# sa_psu.net
KiCad netlist of a schematic drawn in EAGLE
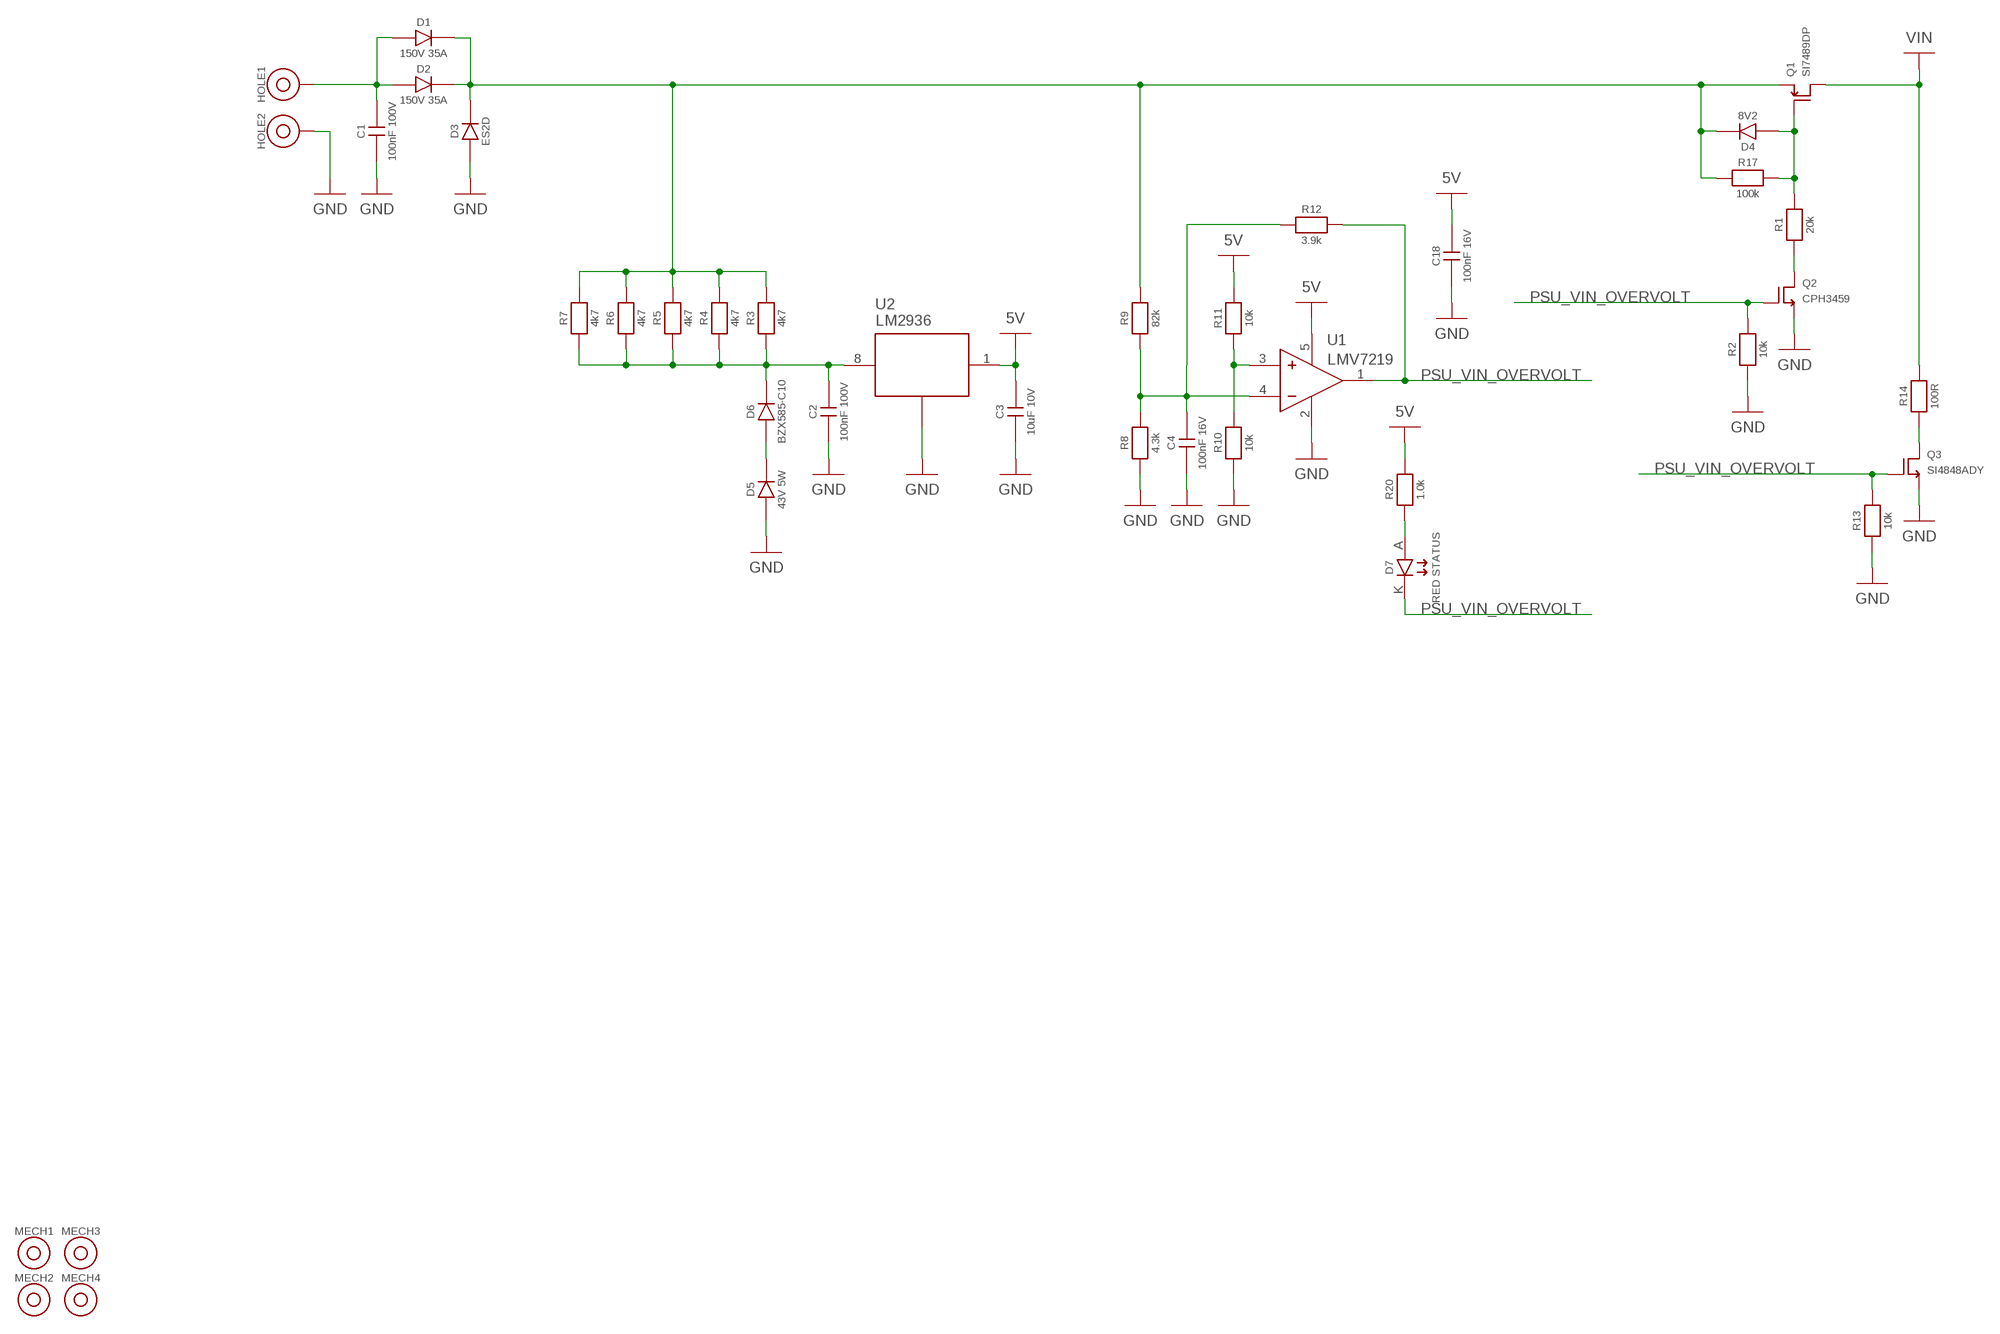
[diagram p0: schematic, sheet 1, part 1 of 2]
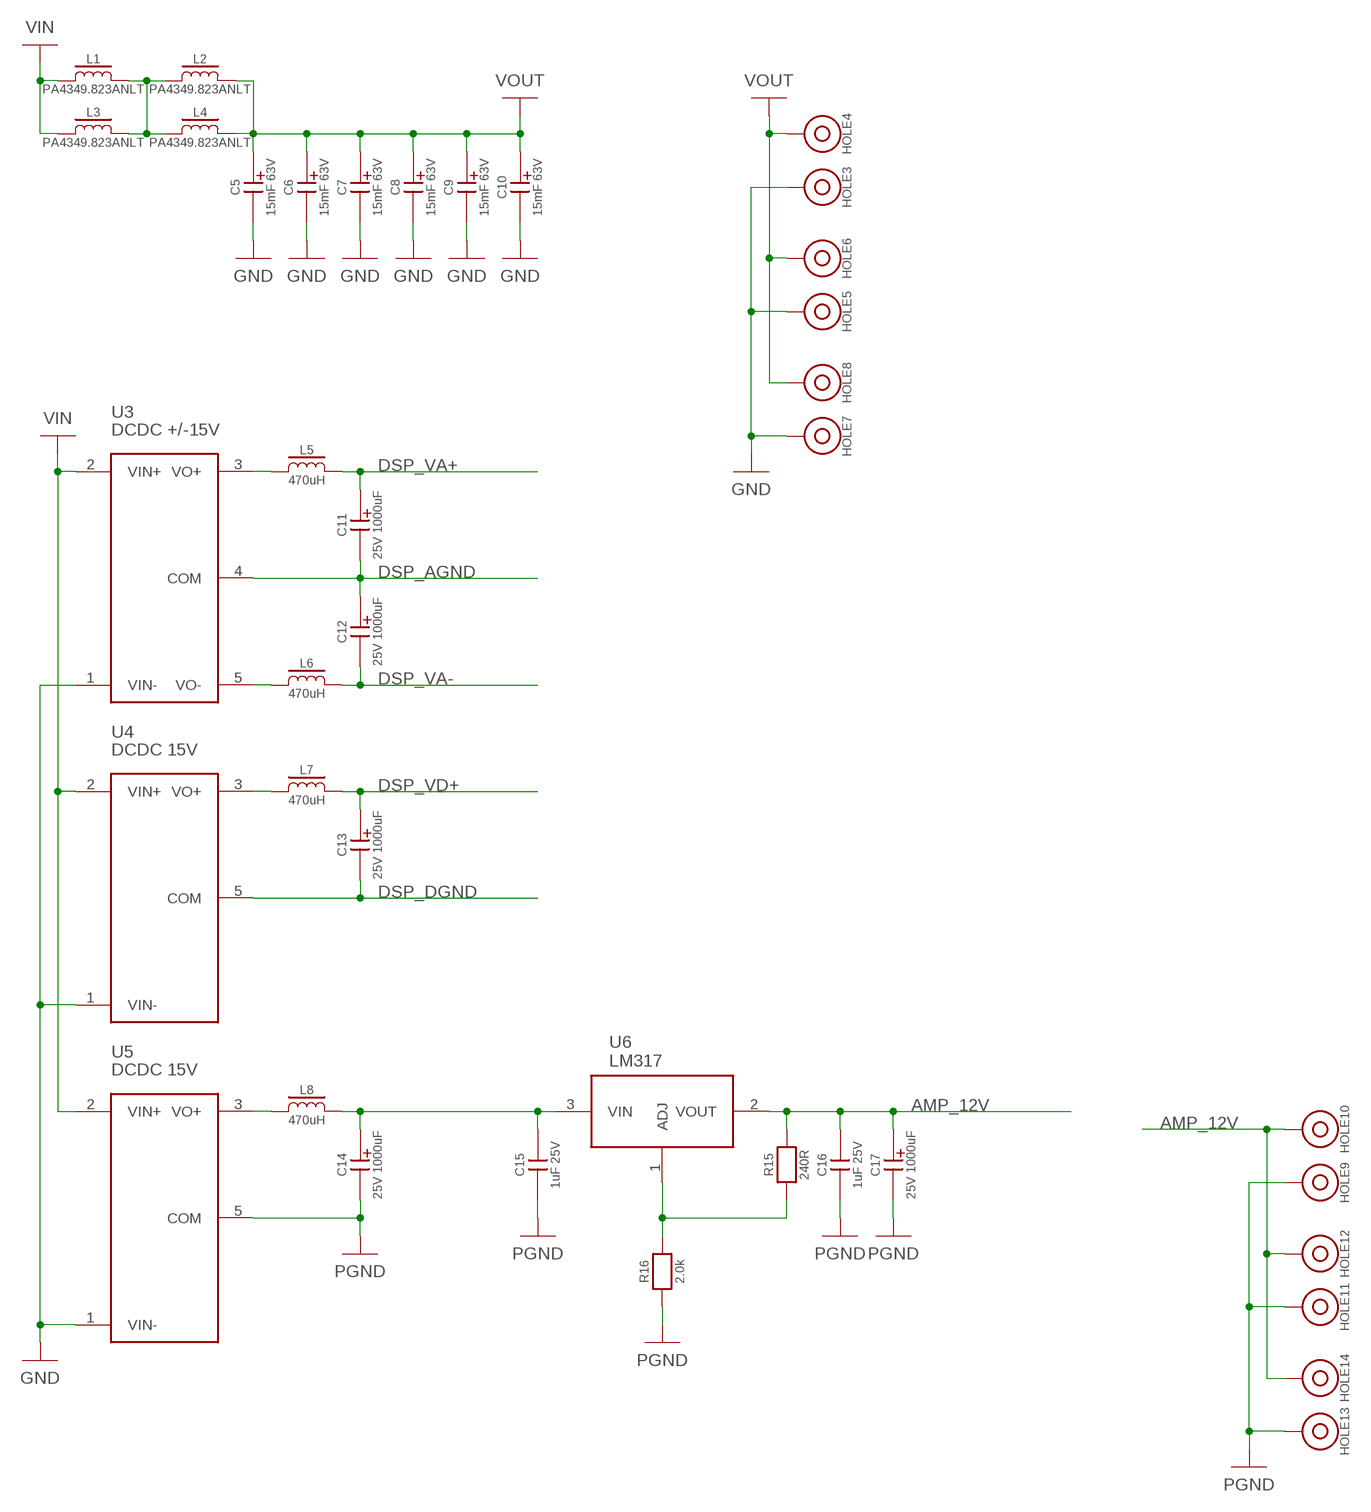
[diagram p1: schematic, sheet 1, part 2 of 2]

(export (version "E")
  (design (tool "Eeschema 10.0.6"))
  (components
    (comp (ref "C1")
      (value "100nF 100V")
      (footprint "eagle-import:0603")
      (libsource (lib "eagle-import") (part "06031C104KAT2A"))
    )
    (comp (ref "C2")
      (value "100nF 100V")
      (footprint "eagle-import:0603")
      (libsource (lib "eagle-import") (part "06031C104KAT2A"))
    )
    (comp (ref "C3")
      (value "10uF 10V")
      (footprint "eagle-import:0603")
      (libsource (lib "eagle-import") (part "GRM188R61A106KE69D"))
    )
    (comp (ref "C4")
      (value "100nF 16V")
      (footprint "eagle-import:0603")
      (libsource (lib "eagle-import") (part "CL10B104KO8WPNC"))
    )
    (comp (ref "C5")
      (value "15mF 63V")
      (footprint "eagle-import:35MM_10MMCAP")
      (libsource (lib "eagle-import") (part "C_ELEC35MM"))
    )
    (comp (ref "C6")
      (value "15mF 63V")
      (footprint "eagle-import:35MM_10MMCAP")
      (libsource (lib "eagle-import") (part "C_ELEC35MM"))
    )
    (comp (ref "C7")
      (value "15mF 63V")
      (footprint "eagle-import:35MM_10MMCAP")
      (libsource (lib "eagle-import") (part "C_ELEC35MM"))
    )
    (comp (ref "C8")
      (value "15mF 63V")
      (footprint "eagle-import:35MM_10MMCAP")
      (libsource (lib "eagle-import") (part "C_ELEC35MM"))
    )
    (comp (ref "C9")
      (value "15mF 63V")
      (footprint "eagle-import:35MM_10MMCAP")
      (libsource (lib "eagle-import") (part "C_ELEC35MM"))
    )
    (comp (ref "C10")
      (value "15mF 63V")
      (footprint "eagle-import:35MM_10MMCAP")
      (libsource (lib "eagle-import") (part "C_ELEC35MM"))
    )
    (comp (ref "C11")
      (value "25V 1000uF")
      (footprint "eagle-import:10MM_RADIAL_5MM_PITCH")
      (libsource (lib "eagle-import") (part "25ZLJ1000M10X20"))
    )
    (comp (ref "C12")
      (value "25V 1000uF")
      (footprint "eagle-import:10MM_RADIAL_5MM_PITCH")
      (libsource (lib "eagle-import") (part "25ZLJ1000M10X20"))
    )
    (comp (ref "C13")
      (value "25V 1000uF")
      (footprint "eagle-import:10MM_RADIAL_5MM_PITCH")
      (libsource (lib "eagle-import") (part "25ZLJ1000M10X20"))
    )
    (comp (ref "C14")
      (value "25V 1000uF")
      (footprint "eagle-import:10MM_RADIAL_5MM_PITCH")
      (libsource (lib "eagle-import") (part "25ZLJ1000M10X20"))
    )
    (comp (ref "C15")
      (value "1uF 25V")
      (footprint "eagle-import:0603")
      (libsource (lib "eagle-import") (part "CL10A105KA8NNNC"))
    )
    (comp (ref "C16")
      (value "1uF 25V")
      (footprint "eagle-import:0603")
      (libsource (lib "eagle-import") (part "CL10A105KA8NNNC"))
    )
    (comp (ref "C17")
      (value "25V 1000uF")
      (footprint "eagle-import:10MM_RADIAL_5MM_PITCH")
      (libsource (lib "eagle-import") (part "25ZLJ1000M10X20"))
    )
    (comp (ref "C18")
      (value "100nF 16V")
      (footprint "eagle-import:0603")
      (libsource (lib "eagle-import") (part "CL10B104KO8WPNC"))
    )
    (comp (ref "D1")
      (value "150V 35A")
      (footprint "eagle-import:TO252")
      (libsource (lib "eagle-import") (part "V35PW15-M3/I"))
    )
    (comp (ref "D2")
      (value "150V 35A")
      (footprint "eagle-import:TO252")
      (libsource (lib "eagle-import") (part "V35PW15-M3/I"))
    )
    (comp (ref "D3")
      (value "ES2D")
      (footprint "eagle-import:DO214AA")
      (libsource (lib "eagle-import") (part "ES2D"))
    )
    (comp (ref "D4")
      (value "8V2")
      (footprint "eagle-import:SOD80")
      (libsource (lib "eagle-import") (part "BZT55C8V2"))
    )
    (comp (ref "D5")
      (value "43V 5W")
      (footprint "eagle-import:017AA-01")
      (libsource (lib "eagle-import") (part "1N5367BG"))
    )
    (comp (ref "D6")
      (value "BZX585-C10")
      (footprint "eagle-import:SOD_523")
      (libsource (lib "eagle-import") (part "BZX585-C10"))
    )
    (comp (ref "D7")
      (value "RED STATUS")
      (footprint "eagle-import:VLMT3100")
      (libsource (lib "eagle-import") (part "VLMT3100-GS08"))
    )
    (comp (ref "HOLE1")
      (value "4mm ID")
      (footprint "eagle-import:MOUNTHOLE_8X4")
      (libsource (lib "eagle-import") (part "MOUNTHOLE_METAL"))
    )
    (comp (ref "HOLE2")
      (value "4mm ID")
      (footprint "eagle-import:MOUNTHOLE_8X4")
      (libsource (lib "eagle-import") (part "MOUNTHOLE_METAL"))
    )
    (comp (ref "HOLE3")
      (value "4mm ID")
      (footprint "eagle-import:MOUNTHOLE_8X4")
      (libsource (lib "eagle-import") (part "MOUNTHOLE_METAL"))
    )
    (comp (ref "HOLE4")
      (value "4mm ID")
      (footprint "eagle-import:MOUNTHOLE_8X4")
      (libsource (lib "eagle-import") (part "MOUNTHOLE_METAL"))
    )
    (comp (ref "HOLE5")
      (value "4mm ID")
      (footprint "eagle-import:MOUNTHOLE_8X4")
      (libsource (lib "eagle-import") (part "MOUNTHOLE_METAL"))
    )
    (comp (ref "HOLE6")
      (value "4mm ID")
      (footprint "eagle-import:MOUNTHOLE_8X4")
      (libsource (lib "eagle-import") (part "MOUNTHOLE_METAL"))
    )
    (comp (ref "HOLE7")
      (value "4mm ID")
      (footprint "eagle-import:MOUNTHOLE_8X4")
      (libsource (lib "eagle-import") (part "MOUNTHOLE_METAL"))
    )
    (comp (ref "HOLE8")
      (value "4mm ID")
      (footprint "eagle-import:MOUNTHOLE_8X4")
      (libsource (lib "eagle-import") (part "MOUNTHOLE_METAL"))
    )
    (comp (ref "HOLE9")
      (value "MOUNTHOLE_METAL4X2")
      (footprint "eagle-import:4X2")
      (libsource (lib "eagle-import") (part "MOUNTHOLE_METAL4X2"))
    )
    (comp (ref "HOLE10")
      (value "MOUNTHOLE_METAL4X2")
      (footprint "eagle-import:4X2")
      (libsource (lib "eagle-import") (part "MOUNTHOLE_METAL4X2"))
    )
    (comp (ref "HOLE11")
      (value "MOUNTHOLE_METAL4X2")
      (footprint "eagle-import:4X2")
      (libsource (lib "eagle-import") (part "MOUNTHOLE_METAL4X2"))
    )
    (comp (ref "HOLE12")
      (value "MOUNTHOLE_METAL4X2")
      (footprint "eagle-import:4X2")
      (libsource (lib "eagle-import") (part "MOUNTHOLE_METAL4X2"))
    )
    (comp (ref "HOLE13")
      (value "MOUNTHOLE_METAL4X2")
      (footprint "eagle-import:4X2")
      (libsource (lib "eagle-import") (part "MOUNTHOLE_METAL4X2"))
    )
    (comp (ref "HOLE14")
      (value "MOUNTHOLE_METAL4X2")
      (footprint "eagle-import:4X2")
      (libsource (lib "eagle-import") (part "MOUNTHOLE_METAL4X2"))
    )
    (comp (ref "L1")
      (value "PA4349.823ANLT")
      (footprint "eagle-import:PA4349.ZZZANLT")
      (libsource (lib "eagle-import") (part "PA4349.823ANLT"))
    )
    (comp (ref "L2")
      (value "PA4349.823ANLT")
      (footprint "eagle-import:PA4349.ZZZANLT")
      (libsource (lib "eagle-import") (part "PA4349.823ANLT"))
    )
    (comp (ref "L3")
      (value "PA4349.823ANLT")
      (footprint "eagle-import:PA4349.ZZZANLT")
      (libsource (lib "eagle-import") (part "PA4349.823ANLT"))
    )
    (comp (ref "L4")
      (value "PA4349.823ANLT")
      (footprint "eagle-import:PA4349.ZZZANLT")
      (libsource (lib "eagle-import") (part "PA4349.823ANLT"))
    )
    (comp (ref "L5")
      (value "470uH")
      (footprint "eagle-import:SRN1060")
      (libsource (lib "eagle-import") (part "SRN1060-471M"))
    )
    (comp (ref "L6")
      (value "470uH")
      (footprint "eagle-import:SRN1060")
      (libsource (lib "eagle-import") (part "SRN1060-471M"))
    )
    (comp (ref "L7")
      (value "470uH")
      (footprint "eagle-import:SRN1060")
      (libsource (lib "eagle-import") (part "SRN1060-471M"))
    )
    (comp (ref "L8")
      (value "470uH")
      (footprint "eagle-import:SRN1060")
      (libsource (lib "eagle-import") (part "SRN1060-471M"))
    )
    (comp (ref "MECH1")
      (value "6mm x 3mm")
      (footprint "eagle-import:MOUNTHOLE_6X3")
      (libsource (lib "eagle-import") (part "MOUNTHOLE"))
    )
    (comp (ref "MECH2")
      (value "6mm x 3mm")
      (footprint "eagle-import:MOUNTHOLE_6X3")
      (libsource (lib "eagle-import") (part "MOUNTHOLE"))
    )
    (comp (ref "MECH3")
      (value "6mm x 3mm")
      (footprint "eagle-import:MOUNTHOLE_6X3")
      (libsource (lib "eagle-import") (part "MOUNTHOLE"))
    )
    (comp (ref "MECH4")
      (value "6mm x 3mm")
      (footprint "eagle-import:MOUNTHOLE_6X3")
      (libsource (lib "eagle-import") (part "MOUNTHOLE"))
    )
    (comp (ref "Q1")
      (value "SI7489DP")
      (footprint "eagle-import:SO8_POWERPAK")
      (libsource (lib "eagle-import") (part "SI7489DP-T1-E3"))
    )
    (comp (ref "Q2")
      (value "CPH3459")
      (footprint "eagle-import:SOT23-3")
      (libsource (lib "eagle-import") (part "CPH3459-TL-W"))
    )
    (comp (ref "Q3")
      (value "SI4848ADY")
      (footprint "eagle-import:SO8")
      (libsource (lib "eagle-import") (part "SI4848ADY-T1-GE3"))
    )
    (comp (ref "R1")
      (value "20k")
      (footprint "eagle-import:0603")
      (libsource (lib "eagle-import") (part "ERJ3EKF2002V"))
    )
    (comp (ref "R2")
      (value "10k")
      (footprint "eagle-import:0603")
      (libsource (lib "eagle-import") (part "ERJ3EKF1002V"))
    )
    (comp (ref "R3")
      (value "4k7")
      (footprint "eagle-import:1206")
      (libsource (lib "eagle-import") (part "CRCW12064K70FKEAHP"))
    )
    (comp (ref "R4")
      (value "4k7")
      (footprint "eagle-import:1206")
      (libsource (lib "eagle-import") (part "CRCW12064K70FKEAHP"))
    )
    (comp (ref "R5")
      (value "4k7")
      (footprint "eagle-import:1206")
      (libsource (lib "eagle-import") (part "CRCW12064K70FKEAHP"))
    )
    (comp (ref "R6")
      (value "4k7")
      (footprint "eagle-import:1206")
      (libsource (lib "eagle-import") (part "CRCW12064K70FKEAHP"))
    )
    (comp (ref "R7")
      (value "4k7")
      (footprint "eagle-import:1206")
      (libsource (lib "eagle-import") (part "CRCW12064K70FKEAHP"))
    )
    (comp (ref "R8")
      (value "4.3k")
      (footprint "eagle-import:0603")
      (libsource (lib "eagle-import") (part "ERJ3EKF4301V"))
    )
    (comp (ref "R9")
      (value "82k")
      (footprint "eagle-import:0603")
      (libsource (lib "eagle-import") (part "ERJ3EKF8202V"))
    )
    (comp (ref "R10")
      (value "10k")
      (footprint "eagle-import:0603")
      (libsource (lib "eagle-import") (part "ERJ3EKF1002V"))
    )
    (comp (ref "R11")
      (value "10k")
      (footprint "eagle-import:0603")
      (libsource (lib "eagle-import") (part "ERJ3EKF1002V"))
    )
    (comp (ref "R12")
      (value "3.9k")
      (footprint "eagle-import:0603")
      (libsource (lib "eagle-import") (part "ERJ3EKF3901V"))
    )
    (comp (ref "R13")
      (value "10k")
      (footprint "eagle-import:0603")
      (libsource (lib "eagle-import") (part "ERJ3EKF1002V"))
    )
    (comp (ref "R14")
      (value "100R")
      (footprint "eagle-import:15MM_TH")
      (libsource (lib "eagle-import") (part "ERG-3SJ101V"))
    )
    (comp (ref "R15")
      (value "240R")
      (footprint "eagle-import:0603")
      (libsource (lib "eagle-import") (part "ERJ3EKF2400V"))
    )
    (comp (ref "R16")
      (value "2.0k")
      (footprint "eagle-import:0603")
      (libsource (lib "eagle-import") (part "ERJ3EKF2001V"))
    )
    (comp (ref "R17")
      (value "100k")
      (footprint "eagle-import:0603")
      (libsource (lib "eagle-import") (part "ERJ3EKF1003V"))
    )
    (comp (ref "R20")
      (value "1.0k")
      (footprint "eagle-import:0603")
      (libsource (lib "eagle-import") (part "ERJ3EKF1001V"))
    )
    (comp (ref "U1")
      (value "LMV7219")
      (footprint "eagle-import:SOT23-5")
      (libsource (lib "eagle-import") (part "LMV7219M5/NOPB"))
    )
    (comp (ref "U2")
      (value "LM2936")
      (footprint "eagle-import:SO8")
      (libsource (lib "eagle-import") (part "LM2936HVMAX"))
    )
    (comp (ref "U3")
      (value "DCDC +/-15V")
      (footprint "eagle-import:PDQE10")
      (libsource (lib "eagle-import") (part "PDQE10-Q48-D15-D"))
    )
    (comp (ref "U4")
      (value "DCDC 15V")
      (footprint "eagle-import:PDQE10")
      (libsource (lib "eagle-import") (part "PDQE10-Q48-S15"))
    )
    (comp (ref "U5")
      (value "DCDC 15V")
      (footprint "eagle-import:PDQE10")
      (libsource (lib "eagle-import") (part "PDQE10-Q48-S15"))
    )
    (comp (ref "U6")
      (value "LM317")
      (footprint "eagle-import:TO220")
      (libsource (lib "eagle-import") (part "LM317T"))
    )
  )
  (nets
    (net (code "1") (name "/AMP_12V") (class "Default")
      (node (ref "C16") (pin "2") (pinfunction "2_2") (pintype "bidirectional"))
      (node (ref "C17") (pin "2") (pinfunction "A_2") (pintype "bidirectional"))
      (node (ref "HOLE10") (pin "1") (pinfunction "1_1") (pintype "bidirectional"))
      (node (ref "HOLE12") (pin "1") (pinfunction "1_1") (pintype "bidirectional"))
      (node (ref "HOLE14") (pin "1") (pinfunction "1_1") (pintype "bidirectional"))
      (node (ref "R15") (pin "2") (pinfunction "2_2") (pintype "bidirectional"))
      (node (ref "U6") (pin "2") (pinfunction "VOUT_2") (pintype "bidirectional"))
    )
    (net (code "2") (name "/DSP_AGND") (class "Default")
      (node (ref "C11") (pin "1") (pinfunction "K_1") (pintype "bidirectional"))
      (node (ref "C12") (pin "2") (pinfunction "A_2") (pintype "bidirectional"))
      (node (ref "U3") (pin "4") (pinfunction "COM_4") (pintype "bidirectional"))
    )
    (net (code "3") (name "/DSP_DGND") (class "Default")
      (node (ref "C13") (pin "1") (pinfunction "K_1") (pintype "bidirectional"))
      (node (ref "U4") (pin "5") (pinfunction "COM_5") (pintype "bidirectional"))
    )
    (net (code "4") (name "/DSP_VA+") (class "Default")
      (node (ref "C11") (pin "2") (pinfunction "A_2") (pintype "bidirectional"))
      (node (ref "L5") (pin "2") (pinfunction "2_2") (pintype "bidirectional"))
    )
    (net (code "5") (name "/DSP_VA-") (class "Default")
      (node (ref "C12") (pin "1") (pinfunction "K_1") (pintype "bidirectional"))
      (node (ref "L6") (pin "2") (pinfunction "2_2") (pintype "bidirectional"))
    )
    (net (code "6") (name "/DSP_VD+") (class "Default")
      (node (ref "C13") (pin "2") (pinfunction "A_2") (pintype "bidirectional"))
      (node (ref "L7") (pin "2") (pinfunction "2_2") (pintype "bidirectional"))
    )
    (net (code "7") (name "/PSU_VIN_OVERVOLT") (class "Default")
      (node (ref "D7") (pin "K") (pinfunction "K_K") (pintype "bidirectional"))
      (node (ref "Q2") (pin "1") (pinfunction "G_1") (pintype "bidirectional"))
      (node (ref "Q3") (pin "4") (pinfunction "G_4") (pintype "bidirectional"))
      (node (ref "R12") (pin "2") (pinfunction "2_2") (pintype "bidirectional"))
      (node (ref "R13") (pin "2") (pinfunction "2_2") (pintype "bidirectional"))
      (node (ref "R2") (pin "2") (pinfunction "2_2") (pintype "bidirectional"))
      (node (ref "U1") (pin "1") (pinfunction "VOUT_1") (pintype "bidirectional"))
    )
    (net (code "8") (name "5V") (class "Default")
      (node (ref "C18") (pin "2") (pinfunction "2_2") (pintype "bidirectional"))
      (node (ref "C3") (pin "2") (pinfunction "2_2") (pintype "bidirectional"))
      (node (ref "R11") (pin "2") (pinfunction "2_2") (pintype "bidirectional"))
      (node (ref "R20") (pin "2") (pinfunction "2_2") (pintype "bidirectional"))
      (node (ref "U1") (pin "5") (pinfunction "VCC_5") (pintype "bidirectional"))
      (node (ref "U2") (pin "1") (pinfunction "VOUT_1") (pintype "bidirectional"))
    )
    (net (code "9") (name "GND") (class "Default")
      (node (ref "C1") (pin "1") (pinfunction "1_1") (pintype "bidirectional"))
      (node (ref "C10") (pin "P$2") (pinfunction "2_P$2") (pintype "bidirectional"))
      (node (ref "C18") (pin "1") (pinfunction "1_1") (pintype "bidirectional"))
      (node (ref "C2") (pin "1") (pinfunction "1_1") (pintype "bidirectional"))
      (node (ref "C3") (pin "1") (pinfunction "1_1") (pintype "bidirectional"))
      (node (ref "C4") (pin "1") (pinfunction "1_1") (pintype "bidirectional"))
      (node (ref "C5") (pin "P$2") (pinfunction "2_P$2") (pintype "bidirectional"))
      (node (ref "C6") (pin "P$2") (pinfunction "2_P$2") (pintype "bidirectional"))
      (node (ref "C7") (pin "P$2") (pinfunction "2_P$2") (pintype "bidirectional"))
      (node (ref "C8") (pin "P$2") (pinfunction "2_P$2") (pintype "bidirectional"))
      (node (ref "C9") (pin "P$2") (pinfunction "2_P$2") (pintype "bidirectional"))
      (node (ref "D3") (pin "A") (pinfunction "A_A") (pintype "bidirectional"))
      (node (ref "D5") (pin "A") (pinfunction "A_A") (pintype "bidirectional"))
      (node (ref "HOLE2") (pin "1") (pinfunction "1_1") (pintype "bidirectional"))
      (node (ref "HOLE3") (pin "1") (pinfunction "1_1") (pintype "bidirectional"))
      (node (ref "HOLE5") (pin "1") (pinfunction "1_1") (pintype "bidirectional"))
      (node (ref "HOLE7") (pin "1") (pinfunction "1_1") (pintype "bidirectional"))
      (node (ref "Q2") (pin "3") (pinfunction "S_3") (pintype "bidirectional"))
      (node (ref "Q3") (pin "1") (pinfunction "S_1") (pintype "bidirectional"))
      (node (ref "Q3") (pin "2") (pinfunction "S_2") (pintype "bidirectional"))
      (node (ref "Q3") (pin "3") (pinfunction "S_3") (pintype "bidirectional"))
      (node (ref "R10") (pin "1") (pinfunction "1_1") (pintype "bidirectional"))
      (node (ref "R13") (pin "1") (pinfunction "1_1") (pintype "bidirectional"))
      (node (ref "R2") (pin "1") (pinfunction "1_1") (pintype "bidirectional"))
      (node (ref "R8") (pin "1") (pinfunction "1_1") (pintype "bidirectional"))
      (node (ref "U1") (pin "2") (pinfunction "GND_2") (pintype "bidirectional"))
      (node (ref "U2") (pin "2") (pinfunction "GND_2") (pintype "bidirectional"))
      (node (ref "U2") (pin "3") (pinfunction "GND_3") (pintype "bidirectional"))
      (node (ref "U2") (pin "6") (pinfunction "GND_6") (pintype "bidirectional"))
      (node (ref "U2") (pin "7") (pinfunction "GND_7") (pintype "bidirectional"))
      (node (ref "U3") (pin "1") (pinfunction "VIN-_1") (pintype "bidirectional"))
      (node (ref "U4") (pin "1") (pinfunction "VIN-_1") (pintype "bidirectional"))
      (node (ref "U5") (pin "1") (pinfunction "VIN-_1") (pintype "bidirectional"))
    )
    (net (code "10") (name "Net-(C1-Pad2)") (class "Default")
      (node (ref "C1") (pin "2") (pinfunction "2_2") (pintype "bidirectional"))
      (node (ref "D1") (pin "1") (pinfunction "A_1") (pintype "bidirectional"))
      (node (ref "D1") (pin "3") (pinfunction "A_3") (pintype "bidirectional"))
      (node (ref "D2") (pin "1") (pinfunction "A_1") (pintype "bidirectional"))
      (node (ref "D2") (pin "3") (pinfunction "A_3") (pintype "bidirectional"))
      (node (ref "HOLE1") (pin "1") (pinfunction "1_1") (pintype "bidirectional"))
    )
    (net (code "11") (name "Net-(C14-A)") (class "Default")
      (node (ref "C14") (pin "2") (pinfunction "A_2") (pintype "bidirectional"))
      (node (ref "C15") (pin "2") (pinfunction "2_2") (pintype "bidirectional"))
      (node (ref "L8") (pin "2") (pinfunction "2_2") (pintype "bidirectional"))
      (node (ref "U6") (pin "3") (pinfunction "VIN_3") (pintype "bidirectional"))
    )
    (net (code "12") (name "Net-(D1-K)") (class "Default")
      (node (ref "D1") (pin "4") (pinfunction "K_4") (pintype "bidirectional"))
      (node (ref "D2") (pin "4") (pinfunction "K_4") (pintype "bidirectional"))
      (node (ref "D3") (pin "K") (pinfunction "K_K") (pintype "bidirectional"))
      (node (ref "D4") (pin "K") (pinfunction "K_K") (pintype "bidirectional"))
      (node (ref "Q1") (pin "1") (pinfunction "S_1") (pintype "bidirectional"))
      (node (ref "Q1") (pin "2") (pinfunction "S_2") (pintype "bidirectional"))
      (node (ref "Q1") (pin "3") (pinfunction "S_3") (pintype "bidirectional"))
      (node (ref "R17") (pin "1") (pinfunction "1_1") (pintype "bidirectional"))
      (node (ref "R3") (pin "2") (pinfunction "2_2") (pintype "bidirectional"))
      (node (ref "R4") (pin "2") (pinfunction "2_2") (pintype "bidirectional"))
      (node (ref "R5") (pin "2") (pinfunction "2_2") (pintype "bidirectional"))
      (node (ref "R6") (pin "2") (pinfunction "2_2") (pintype "bidirectional"))
      (node (ref "R7") (pin "2") (pinfunction "2_2") (pintype "bidirectional"))
      (node (ref "R9") (pin "2") (pinfunction "2_2") (pintype "bidirectional"))
    )
    (net (code "13") (name "Net-(D5-PadK)") (class "Default")
      (node (ref "D5") (pin "K") (pinfunction "K_K") (pintype "bidirectional"))
      (node (ref "D6") (pin "A") (pinfunction "A_A") (pintype "bidirectional"))
    )
    (net (code "14") (name "Net-(D7-PadA)") (class "Default")
      (node (ref "D7") (pin "A") (pinfunction "A_A") (pintype "bidirectional"))
      (node (ref "R20") (pin "1") (pinfunction "1_1") (pintype "bidirectional"))
    )
    (net (code "15") (name "Net-(L1-Pad2)") (class "Default")
      (node (ref "L1") (pin "2") (pinfunction "2_2") (pintype "bidirectional"))
      (node (ref "L2") (pin "1") (pinfunction "1_1") (pintype "bidirectional"))
      (node (ref "L3") (pin "2") (pinfunction "2_2") (pintype "bidirectional"))
      (node (ref "L4") (pin "1") (pinfunction "1_1") (pintype "bidirectional"))
    )
    (net (code "16") (name "Net-(Q1-G)") (class "Default")
      (node (ref "D4") (pin "A") (pinfunction "A_A") (pintype "bidirectional"))
      (node (ref "Q1") (pin "4") (pinfunction "G_4") (pintype "bidirectional"))
      (node (ref "R1") (pin "2") (pinfunction "2_2") (pintype "bidirectional"))
      (node (ref "R17") (pin "2") (pinfunction "2_2") (pintype "bidirectional"))
    )
    (net (code "17") (name "Net-(Q2-D)") (class "Default")
      (node (ref "Q2") (pin "2") (pinfunction "D_2") (pintype "bidirectional"))
      (node (ref "R1") (pin "1") (pinfunction "1_1") (pintype "bidirectional"))
    )
    (net (code "18") (name "Net-(Q3-D-Pad5)") (class "Default")
      (node (ref "Q3") (pin "5") (pinfunction "D_5") (pintype "bidirectional"))
      (node (ref "Q3") (pin "6") (pinfunction "D_6") (pintype "bidirectional"))
      (node (ref "Q3") (pin "7") (pinfunction "D_7") (pintype "bidirectional"))
      (node (ref "Q3") (pin "8") (pinfunction "D_8") (pintype "bidirectional"))
      (node (ref "R14") (pin "1") (pinfunction "1_1") (pintype "bidirectional"))
    )
    (net (code "19") (name "Net-(U1-+)") (class "Default")
      (node (ref "R10") (pin "2") (pinfunction "2_2") (pintype "bidirectional"))
      (node (ref "R11") (pin "1") (pinfunction "1_1") (pintype "bidirectional"))
      (node (ref "U1") (pin "3") (pinfunction "+_3") (pintype "bidirectional"))
    )
    (net (code "20") (name "Net-(U1--)") (class "Default")
      (node (ref "C4") (pin "2") (pinfunction "2_2") (pintype "bidirectional"))
      (node (ref "R12") (pin "1") (pinfunction "1_1") (pintype "bidirectional"))
      (node (ref "R8") (pin "2") (pinfunction "2_2") (pintype "bidirectional"))
      (node (ref "R9") (pin "1") (pinfunction "1_1") (pintype "bidirectional"))
      (node (ref "U1") (pin "4") (pinfunction "-_4") (pintype "bidirectional"))
    )
    (net (code "21") (name "Net-(U2-VIN)") (class "Default")
      (node (ref "C2") (pin "2") (pinfunction "2_2") (pintype "bidirectional"))
      (node (ref "D6") (pin "K") (pinfunction "K_K") (pintype "bidirectional"))
      (node (ref "R3") (pin "1") (pinfunction "1_1") (pintype "bidirectional"))
      (node (ref "R4") (pin "1") (pinfunction "1_1") (pintype "bidirectional"))
      (node (ref "R5") (pin "1") (pinfunction "1_1") (pintype "bidirectional"))
      (node (ref "R6") (pin "1") (pinfunction "1_1") (pintype "bidirectional"))
      (node (ref "R7") (pin "1") (pinfunction "1_1") (pintype "bidirectional"))
      (node (ref "U2") (pin "8") (pinfunction "VIN_8") (pintype "bidirectional"))
    )
    (net (code "22") (name "Net-(U3-VO+)") (class "Default")
      (node (ref "L5") (pin "1") (pinfunction "1_1") (pintype "bidirectional"))
      (node (ref "U3") (pin "3") (pinfunction "VO+_3") (pintype "bidirectional"))
    )
    (net (code "23") (name "Net-(U3-VO-)") (class "Default")
      (node (ref "L6") (pin "1") (pinfunction "1_1") (pintype "bidirectional"))
      (node (ref "U3") (pin "5") (pinfunction "VO-_5") (pintype "bidirectional"))
    )
    (net (code "24") (name "Net-(U4-VO+)") (class "Default")
      (node (ref "L7") (pin "1") (pinfunction "1_1") (pintype "bidirectional"))
      (node (ref "U4") (pin "3") (pinfunction "VO+_3") (pintype "bidirectional"))
    )
    (net (code "25") (name "Net-(U5-VO+)") (class "Default")
      (node (ref "L8") (pin "1") (pinfunction "1_1") (pintype "bidirectional"))
      (node (ref "U5") (pin "3") (pinfunction "VO+_3") (pintype "bidirectional"))
    )
    (net (code "26") (name "Net-(U6-ADJ)") (class "Default")
      (node (ref "R15") (pin "1") (pinfunction "1_1") (pintype "bidirectional"))
      (node (ref "R16") (pin "2") (pinfunction "2_2") (pintype "bidirectional"))
      (node (ref "U6") (pin "1") (pinfunction "ADJ_1") (pintype "bidirectional"))
    )
    (net (code "27") (name "PGND") (class "Default")
      (node (ref "C14") (pin "1") (pinfunction "K_1") (pintype "bidirectional"))
      (node (ref "C15") (pin "1") (pinfunction "1_1") (pintype "bidirectional"))
      (node (ref "C16") (pin "1") (pinfunction "1_1") (pintype "bidirectional"))
      (node (ref "C17") (pin "1") (pinfunction "K_1") (pintype "bidirectional"))
      (node (ref "HOLE11") (pin "1") (pinfunction "1_1") (pintype "bidirectional"))
      (node (ref "HOLE13") (pin "1") (pinfunction "1_1") (pintype "bidirectional"))
      (node (ref "HOLE9") (pin "1") (pinfunction "1_1") (pintype "bidirectional"))
      (node (ref "R16") (pin "1") (pinfunction "1_1") (pintype "bidirectional"))
      (node (ref "U5") (pin "5") (pinfunction "COM_5") (pintype "bidirectional"))
    )
    (net (code "28") (name "VIN") (class "Default")
      (node (ref "L1") (pin "1") (pinfunction "1_1") (pintype "bidirectional"))
      (node (ref "L3") (pin "1") (pinfunction "1_1") (pintype "bidirectional"))
      (node (ref "Q1") (pin "5") (pinfunction "D_5") (pintype "bidirectional"))
      (node (ref "Q1") (pin "6") (pinfunction "D_6") (pintype "bidirectional"))
      (node (ref "Q1") (pin "7") (pinfunction "D_7") (pintype "bidirectional"))
      (node (ref "Q1") (pin "8") (pinfunction "D_8") (pintype "bidirectional"))
      (node (ref "Q1") (pin "PAD") (pinfunction "D_PAD") (pintype "bidirectional"))
      (node (ref "R14") (pin "2") (pinfunction "2_2") (pintype "bidirectional"))
      (node (ref "U3") (pin "2") (pinfunction "VIN+_2") (pintype "bidirectional"))
      (node (ref "U4") (pin "2") (pinfunction "VIN+_2") (pintype "bidirectional"))
      (node (ref "U5") (pin "2") (pinfunction "VIN+_2") (pintype "bidirectional"))
    )
    (net (code "29") (name "VOUT") (class "Default")
      (node (ref "C10") (pin "P$1") (pinfunction "1_P$1") (pintype "bidirectional"))
      (node (ref "C5") (pin "P$1") (pinfunction "1_P$1") (pintype "bidirectional"))
      (node (ref "C6") (pin "P$1") (pinfunction "1_P$1") (pintype "bidirectional"))
      (node (ref "C7") (pin "P$1") (pinfunction "1_P$1") (pintype "bidirectional"))
      (node (ref "C8") (pin "P$1") (pinfunction "1_P$1") (pintype "bidirectional"))
      (node (ref "C9") (pin "P$1") (pinfunction "1_P$1") (pintype "bidirectional"))
      (node (ref "HOLE4") (pin "1") (pinfunction "1_1") (pintype "bidirectional"))
      (node (ref "HOLE6") (pin "1") (pinfunction "1_1") (pintype "bidirectional"))
      (node (ref "HOLE8") (pin "1") (pinfunction "1_1") (pintype "bidirectional"))
      (node (ref "L2") (pin "2") (pinfunction "2_2") (pintype "bidirectional"))
      (node (ref "L4") (pin "2") (pinfunction "2_2") (pintype "bidirectional"))
    )
  )
)
